# simple-loop-active.net
KiCad netlist of a schematic drawn in EAGLE
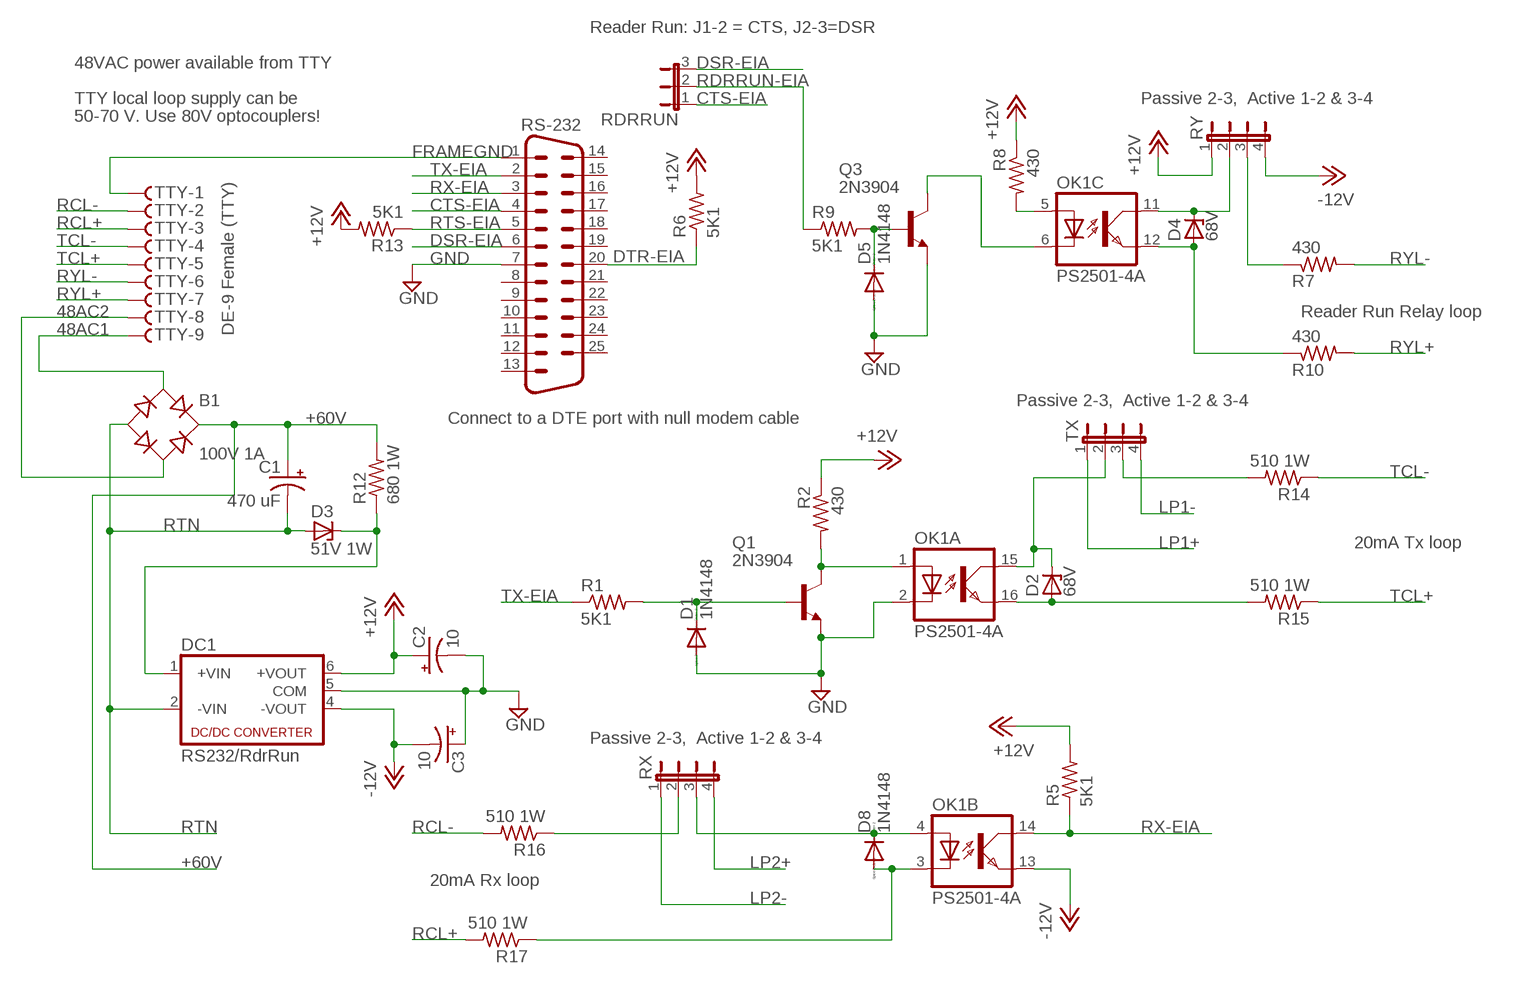
[diagram p0: schematic, sheet 1]
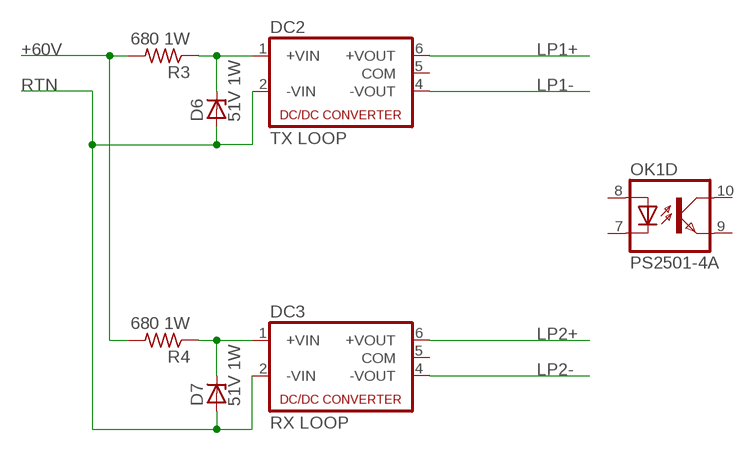
[diagram p1: schematic, sheet 2]

(export (version "E")
  (design (tool "Eeschema 10.0.6"))
  (components
    (comp (ref "D6")
      (value "51V 1W")
      (footprint "eagle-import:DO41Z10")
      (libsource (lib "eagle-import") (part "ZENER-DIODEDO41Z10"))
    )
    (comp (ref "D7")
      (value "51V 1W")
      (footprint "eagle-import:DO41Z10")
      (libsource (lib "eagle-import") (part "ZENER-DIODEDO41Z10"))
    )
    (comp (ref "DC2")
      (value "TX LOOP")
      (footprint "eagle-import:NMA")
      (fields (field (name "MF") "C & D TECHNOLOGIES, INC") (field (name "MPN") "NMA0515SC"))
      (libsource (lib "eagle-import") (part "NMA"))
    )
    (comp (ref "DC3")
      (value "RX LOOP")
      (footprint "eagle-import:NMA")
      (fields (field (name "MF") "C & D TECHNOLOGIES, INC") (field (name "MPN") "NMA0515SC"))
      (libsource (lib "eagle-import") (part "NMA"))
    )
    (comp (ref "OK1")
      (value "PS2501-4A")
      (footprint "eagle-import:DIL16")
      (fields (field (name "MF") "VISHAY/TELEFUNKEN") (field (name "MPN") "ILQ1"))
      (libsource (lib "eagle-import") (part "ILQ1"))
    )
    (comp (ref "R3")
      (value "680 1W")
      (footprint "eagle-import:P0817V")
      (libsource (lib "eagle-import") (part "R-US_0817/7V"))
    )
    (comp (ref "R4")
      (value "680 1W")
      (footprint "eagle-import:P0817V")
      (libsource (lib "eagle-import") (part "R-US_0817/7V"))
    )
    (comp (ref "B1")
      (value "100V 1A")
      (footprint "eagle-import:RB1A")
      (libsource (lib "eagle-import") (part "RB1A"))
    )
    (comp (ref "C1")
      (value "470 uF")
      (footprint "eagle-import:E7,5-18")
      (libsource (lib "eagle-import") (part "CPOL-USE7.5-18"))
    )
    (comp (ref "C2")
      (value "10")
      (footprint "eagle-import:B45181A")
      (libsource (lib "eagle-import") (part "CPOL-USB45181A"))
    )
    (comp (ref "C3")
      (value "10")
      (footprint "eagle-import:B45181A")
      (libsource (lib "eagle-import") (part "CPOL-USB45181A"))
    )
    (comp (ref "D1")
      (value "1N4148")
      (footprint "eagle-import:DO35-10")
      (libsource (lib "eagle-import") (part "1N4148DO35-10"))
    )
    (comp (ref "D2")
      (value "68V")
      (footprint "eagle-import:DO41Z10")
      (libsource (lib "eagle-import") (part "ZENER-DIODEDO41Z10"))
    )
    (comp (ref "D3")
      (value "51V 1W")
      (footprint "eagle-import:DO41Z10")
      (libsource (lib "eagle-import") (part "ZENER-DIODEDO41Z10"))
    )
    (comp (ref "D4")
      (value "68V")
      (footprint "eagle-import:DO41Z10")
      (libsource (lib "eagle-import") (part "ZENER-DIODEDO41Z10"))
    )
    (comp (ref "D5")
      (value "1N4148")
      (footprint "eagle-import:DO35-10")
      (libsource (lib "eagle-import") (part "1N4148DO35-10"))
    )
    (comp (ref "D8")
      (value "1N4148")
      (footprint "eagle-import:DO35-10")
      (libsource (lib "eagle-import") (part "1N4148DO35-10"))
    )
    (comp (ref "DC1")
      (value "RS232/RdrRun")
      (footprint "eagle-import:NMA")
      (fields (field (name "MF") "C & D TECHNOLOGIES, INC") (field (name "MPN") "NMA0515SC"))
      (libsource (lib "eagle-import") (part "NMA"))
    )
    (comp (ref "Q1")
      (value "2N3904")
      (footprint "eagle-import:TO92")
      (libsource (lib "eagle-import") (part "2N3904"))
    )
    (comp (ref "Q3")
      (value "2N3904")
      (footprint "eagle-import:TO92")
      (libsource (lib "eagle-import") (part "2N3904"))
    )
    (comp (ref "R1")
      (value "5K1")
      (footprint "eagle-import:0207_10")
      (libsource (lib "eagle-import") (part "R-US_0207/10"))
    )
    (comp (ref "R2")
      (value "430")
      (footprint "eagle-import:0207_10")
      (libsource (lib "eagle-import") (part "R-US_0207/10"))
    )
    (comp (ref "R5")
      (value "5K1")
      (footprint "eagle-import:0207_10")
      (libsource (lib "eagle-import") (part "R-US_0207/10"))
    )
    (comp (ref "R6")
      (value "5K1")
      (footprint "eagle-import:0207_10")
      (libsource (lib "eagle-import") (part "R-US_0207/10"))
    )
    (comp (ref "R7")
      (value "430")
      (footprint "eagle-import:0207_10")
      (libsource (lib "eagle-import") (part "R-US_0207/10"))
    )
    (comp (ref "R8")
      (value "430")
      (footprint "eagle-import:0207_10")
      (libsource (lib "eagle-import") (part "R-US_0207/10"))
    )
    (comp (ref "R9")
      (value "5K1")
      (footprint "eagle-import:0207_10")
      (libsource (lib "eagle-import") (part "R-US_0207/10"))
    )
    (comp (ref "R10")
      (value "430")
      (footprint "eagle-import:0207_10")
      (libsource (lib "eagle-import") (part "R-US_0207/10"))
    )
    (comp (ref "R12")
      (value "680 1W")
      (footprint "eagle-import:P0817V")
      (libsource (lib "eagle-import") (part "R-US_0817/7V"))
    )
    (comp (ref "R13")
      (value "5K1")
      (footprint "eagle-import:0207_10")
      (libsource (lib "eagle-import") (part "R-US_0207/10"))
    )
    (comp (ref "R14")
      (value "510 1W")
      (footprint "eagle-import:P0817V")
      (libsource (lib "eagle-import") (part "R-US_0817/7V"))
    )
    (comp (ref "R15")
      (value "510 1W")
      (footprint "eagle-import:P0817V")
      (libsource (lib "eagle-import") (part "R-US_0817/7V"))
    )
    (comp (ref "R16")
      (value "510 1W")
      (footprint "eagle-import:P0817V")
      (libsource (lib "eagle-import") (part "R-US_0817/7V"))
    )
    (comp (ref "R17")
      (value "510 1W")
      (footprint "eagle-import:P0817V")
      (libsource (lib "eagle-import") (part "R-US_0817/7V"))
    )
    (comp (ref "RDRRUN")
      (value "JP2E")
      (footprint "eagle-import:JP2")
      (libsource (lib "eagle-import") (part "JP2E"))
    )
    (comp (ref "RS-232")
      (value "M25H")
      (footprint "eagle-import:M25H")
      (libsource (lib "eagle-import") (part "M25H"))
    )
    (comp (ref "RX")
      (value "JP4E")
      (footprint "eagle-import:JP4")
      (libsource (lib "eagle-import") (part "JP4E"))
    )
    (comp (ref "RY")
      (value "JP4E")
      (footprint "eagle-import:JP4")
      (libsource (lib "eagle-import") (part "JP4E"))
    )
    (comp (ref "TTY")
      (value "F09HS")
      (footprint "eagle-import:F09H")
      (libsource (lib "eagle-import") (part "F09?SH"))
    )
    (comp (ref "TX")
      (value "JP4E")
      (footprint "eagle-import:JP4")
      (libsource (lib "eagle-import") (part "JP4E"))
    )
  )
  (nets
    (net (code "1") (name "+12V") (class "Default")
      (node (ref "C2") (pin "+") (pinfunction "+_+") (pintype "passive"))
      (node (ref "DC1") (pin "6") (pinfunction "+VOUT_6") (pintype "passive"))
      (node (ref "R13") (pin "2") (pinfunction "2_2") (pintype "passive"))
      (node (ref "R2") (pin "1") (pinfunction "1_1") (pintype "passive"))
      (node (ref "R5") (pin "2") (pinfunction "2_2") (pintype "passive"))
      (node (ref "R6") (pin "2") (pinfunction "2_2") (pintype "passive"))
      (node (ref "R8") (pin "1") (pinfunction "1_1") (pintype "passive"))
      (node (ref "RY") (pin "1") (pinfunction "1_1") (pintype "passive"))
    )
    (net (code "2") (name "+60V") (class "Default")
      (node (ref "B1") (pin "+") (pinfunction "+_+") (pintype "passive"))
      (node (ref "C1") (pin "+") (pinfunction "+_+") (pintype "passive"))
      (node (ref "R12") (pin "2") (pinfunction "2_2") (pintype "passive"))
      (node (ref "R3") (pin "2") (pinfunction "2_2") (pintype "passive"))
      (node (ref "R4") (pin "2") (pinfunction "2_2") (pintype "passive"))
    )
    (net (code "3") (name "-12V") (class "Default")
      (node (ref "C3") (pin "-") (pinfunction "-_-") (pintype "passive"))
      (node (ref "DC1") (pin "4") (pinfunction "-VOUT_4") (pintype "passive"))
      (node (ref "OK1") (pin "13") (pinfunction "EMIT_13") (pintype "passive"))
      (node (ref "RY") (pin "4") (pinfunction "4_4") (pintype "passive"))
    )
    (net (code "4") (name "48AC1") (class "Default")
      (node (ref "B1") (pin "AC1") (pinfunction "AC1_AC1") (pintype "passive"))
      (node (ref "TTY") (pin "9") (pinfunction "F_9") (pintype "passive"))
    )
    (net (code "5") (name "48AC2") (class "Default")
      (node (ref "B1") (pin "AC2") (pinfunction "AC2_AC2") (pintype "passive"))
      (node (ref "TTY") (pin "8") (pinfunction "F_8") (pintype "passive"))
    )
    (net (code "6") (name "CTS-EIA") (class "Default")
      (node (ref "RDRRUN") (pin "1") (pinfunction "1_1") (pintype "passive"))
      (node (ref "RS-232") (pin "4") (pinfunction "4_4") (pintype "passive"))
    )
    (net (code "7") (name "DSR-EIA") (class "Default")
      (node (ref "RDRRUN") (pin "3") (pinfunction "3_3") (pintype "passive"))
      (node (ref "RS-232") (pin "6") (pinfunction "6_6") (pintype "passive"))
    )
    (net (code "8") (name "DTR-EIA") (class "Default")
      (node (ref "R6") (pin "1") (pinfunction "1_1") (pintype "passive"))
      (node (ref "RS-232") (pin "20") (pinfunction "20_20") (pintype "passive"))
    )
    (net (code "9") (name "FRAMEGND") (class "Default")
      (node (ref "RS-232") (pin "1") (pinfunction "1_1") (pintype "passive"))
      (node (ref "TTY") (pin "1") (pinfunction "F_1") (pintype "passive"))
    )
    (net (code "10") (name "GND") (class "Default")
      (node (ref "C2") (pin "-") (pinfunction "-_-") (pintype "passive"))
      (node (ref "C3") (pin "+") (pinfunction "+_+") (pintype "passive"))
      (node (ref "D1") (pin "A") (pinfunction "A_A") (pintype "passive"))
      (node (ref "D5") (pin "A") (pinfunction "A_A") (pintype "passive"))
      (node (ref "DC1") (pin "5") (pinfunction "COM_5") (pintype "passive"))
      (node (ref "OK1") (pin "2") (pinfunction "C_2") (pintype "passive"))
      (node (ref "Q1") (pin "3") (pinfunction "E_3") (pintype "passive"))
      (node (ref "Q3") (pin "3") (pinfunction "E_3") (pintype "passive"))
      (node (ref "RS-232") (pin "7") (pinfunction "7_7") (pintype "passive"))
    )
    (net (code "11") (name "LP1+") (class "Default")
      (node (ref "DC2") (pin "6") (pinfunction "+VOUT_6") (pintype "passive"))
      (node (ref "TX") (pin "1") (pinfunction "1_1") (pintype "passive"))
    )
    (net (code "12") (name "LP1-") (class "Default")
      (node (ref "DC2") (pin "4") (pinfunction "-VOUT_4") (pintype "passive"))
      (node (ref "TX") (pin "4") (pinfunction "4_4") (pintype "passive"))
    )
    (net (code "13") (name "LP2+") (class "Default")
      (node (ref "DC3") (pin "6") (pinfunction "+VOUT_6") (pintype "passive"))
      (node (ref "RX") (pin "4") (pinfunction "4_4") (pintype "passive"))
    )
    (net (code "14") (name "LP2-") (class "Default")
      (node (ref "DC3") (pin "4") (pinfunction "-VOUT_4") (pintype "passive"))
      (node (ref "RX") (pin "1") (pinfunction "1_1") (pintype "passive"))
    )
    (net (code "15") (name "Net-(DC1-+VIN)") (class "Default")
      (node (ref "D3") (pin "C") (pinfunction "C_C") (pintype "passive"))
      (node (ref "DC1") (pin "1") (pinfunction "+VIN_1") (pintype "passive"))
      (node (ref "R12") (pin "1") (pinfunction "1_1") (pintype "passive"))
    )
    (net (code "16") (name "Net-(DC2-+VIN)") (class "Default")
      (node (ref "D6") (pin "C") (pinfunction "C_C") (pintype "passive"))
      (node (ref "DC2") (pin "1") (pinfunction "+VIN_1") (pintype "passive"))
      (node (ref "R3") (pin "1") (pinfunction "1_1") (pintype "passive"))
    )
    (net (code "17") (name "Net-(DC3-+VIN)") (class "Default")
      (node (ref "D7") (pin "C") (pinfunction "C_C") (pintype "passive"))
      (node (ref "DC3") (pin "1") (pinfunction "+VIN_1") (pintype "passive"))
      (node (ref "R4") (pin "1") (pinfunction "1_1") (pintype "passive"))
    )
    (net (code "18") (name "Net-(OK1A-A)") (class "Default")
      (node (ref "OK1") (pin "1") (pinfunction "A_1") (pintype "passive"))
      (node (ref "Q1") (pin "1") (pinfunction "C_1") (pintype "passive"))
      (node (ref "R2") (pin "2") (pinfunction "2_2") (pintype "passive"))
    )
    (net (code "19") (name "Net-(OK1A-COL)") (class "Default")
      (node (ref "D2") (pin "C") (pinfunction "C_C") (pintype "passive"))
      (node (ref "OK1") (pin "15") (pinfunction "COL_15") (pintype "passive"))
      (node (ref "TX") (pin "2") (pinfunction "2_2") (pintype "passive"))
    )
    (net (code "20") (name "Net-(OK1A-EMIT)") (class "Default")
      (node (ref "D2") (pin "A") (pinfunction "A_A") (pintype "passive"))
      (node (ref "OK1") (pin "16") (pinfunction "EMIT_16") (pintype "passive"))
      (node (ref "R15") (pin "2") (pinfunction "2_2") (pintype "passive"))
    )
    (net (code "21") (name "Net-(OK1B-A)") (class "Default")
      (node (ref "D8") (pin "C") (pinfunction "C_C") (pintype "passive"))
      (node (ref "OK1") (pin "4") (pinfunction "A_4") (pintype "passive"))
      (node (ref "RX") (pin "3") (pinfunction "3_3") (pintype "passive"))
    )
    (net (code "22") (name "Net-(OK1B-C)") (class "Default")
      (node (ref "D8") (pin "A") (pinfunction "A_A") (pintype "passive"))
      (node (ref "OK1") (pin "3") (pinfunction "C_3") (pintype "passive"))
      (node (ref "R17") (pin "1") (pinfunction "1_1") (pintype "passive"))
    )
    (net (code "23") (name "Net-(OK1C-A)") (class "Default")
      (node (ref "OK1") (pin "5") (pinfunction "A_5") (pintype "passive"))
      (node (ref "R8") (pin "2") (pinfunction "2_2") (pintype "passive"))
    )
    (net (code "24") (name "Net-(OK1C-C)") (class "Default")
      (node (ref "OK1") (pin "6") (pinfunction "C_6") (pintype "passive"))
      (node (ref "Q3") (pin "1") (pinfunction "C_1") (pintype "passive"))
    )
    (net (code "25") (name "Net-(OK1C-COL)") (class "Default")
      (node (ref "D4") (pin "C") (pinfunction "C_C") (pintype "passive"))
      (node (ref "OK1") (pin "11") (pinfunction "COL_11") (pintype "passive"))
      (node (ref "RY") (pin "2") (pinfunction "2_2") (pintype "passive"))
    )
    (net (code "26") (name "Net-(OK1C-EMIT)") (class "Default")
      (node (ref "D4") (pin "A") (pinfunction "A_A") (pintype "passive"))
      (node (ref "OK1") (pin "12") (pinfunction "EMIT_12") (pintype "passive"))
      (node (ref "R10") (pin "1") (pinfunction "1_1") (pintype "passive"))
    )
    (net (code "27") (name "Net-(Q1-B)") (class "Default")
      (node (ref "D1") (pin "C") (pinfunction "C_C") (pintype "passive"))
      (node (ref "Q1") (pin "2") (pinfunction "B_2") (pintype "passive"))
      (node (ref "R1") (pin "2") (pinfunction "2_2") (pintype "passive"))
    )
    (net (code "28") (name "Net-(Q3-B)") (class "Default")
      (node (ref "D5") (pin "C") (pinfunction "C_C") (pintype "passive"))
      (node (ref "Q3") (pin "2") (pinfunction "B_2") (pintype "passive"))
      (node (ref "R9") (pin "2") (pinfunction "2_2") (pintype "passive"))
    )
    (net (code "29") (name "Net-(R7-Pad1)") (class "Default")
      (node (ref "R7") (pin "1") (pinfunction "1_1") (pintype "passive"))
      (node (ref "RY") (pin "3") (pinfunction "3_3") (pintype "passive"))
    )
    (net (code "30") (name "Net-(R14-Pad2)") (class "Default")
      (node (ref "R14") (pin "2") (pinfunction "2_2") (pintype "passive"))
      (node (ref "TX") (pin "3") (pinfunction "3_3") (pintype "passive"))
    )
    (net (code "31") (name "Net-(R16-Pad1)") (class "Default")
      (node (ref "R16") (pin "1") (pinfunction "1_1") (pintype "passive"))
      (node (ref "RX") (pin "2") (pinfunction "2_2") (pintype "passive"))
    )
    (net (code "32") (name "RCL+") (class "Default")
      (node (ref "R17") (pin "2") (pinfunction "2_2") (pintype "passive"))
      (node (ref "TTY") (pin "3") (pinfunction "F_3") (pintype "passive"))
    )
    (net (code "33") (name "RCL-") (class "Default")
      (node (ref "R16") (pin "2") (pinfunction "2_2") (pintype "passive"))
      (node (ref "TTY") (pin "2") (pinfunction "F_2") (pintype "passive"))
    )
    (net (code "34") (name "RDRRUN-EIA") (class "Default")
      (node (ref "R9") (pin "1") (pinfunction "1_1") (pintype "passive"))
      (node (ref "RDRRUN") (pin "2") (pinfunction "2_2") (pintype "passive"))
    )
    (net (code "35") (name "RTN") (class "Default")
      (node (ref "B1") (pin "-") (pinfunction "-_-") (pintype "passive"))
      (node (ref "C1") (pin "-") (pinfunction "-_-") (pintype "passive"))
      (node (ref "D3") (pin "A") (pinfunction "A_A") (pintype "passive"))
      (node (ref "D6") (pin "A") (pinfunction "A_A") (pintype "passive"))
      (node (ref "D7") (pin "A") (pinfunction "A_A") (pintype "passive"))
      (node (ref "DC1") (pin "2") (pinfunction "-VIN_2") (pintype "passive"))
      (node (ref "DC2") (pin "2") (pinfunction "-VIN_2") (pintype "passive"))
      (node (ref "DC3") (pin "2") (pinfunction "-VIN_2") (pintype "passive"))
    )
    (net (code "36") (name "RTS-EIA") (class "Default")
      (node (ref "R13") (pin "1") (pinfunction "1_1") (pintype "passive"))
      (node (ref "RS-232") (pin "5") (pinfunction "5_5") (pintype "passive"))
    )
    (net (code "37") (name "RX-EIA") (class "Default")
      (node (ref "OK1") (pin "14") (pinfunction "COL_14") (pintype "passive"))
      (node (ref "R5") (pin "1") (pinfunction "1_1") (pintype "passive"))
      (node (ref "RS-232") (pin "3") (pinfunction "3_3") (pintype "passive"))
    )
    (net (code "38") (name "RYL+") (class "Default")
      (node (ref "R10") (pin "2") (pinfunction "2_2") (pintype "passive"))
      (node (ref "TTY") (pin "7") (pinfunction "F_7") (pintype "passive"))
    )
    (net (code "39") (name "RYL-") (class "Default")
      (node (ref "R7") (pin "2") (pinfunction "2_2") (pintype "passive"))
      (node (ref "TTY") (pin "6") (pinfunction "F_6") (pintype "passive"))
    )
    (net (code "40") (name "TCL+") (class "Default")
      (node (ref "R15") (pin "1") (pinfunction "1_1") (pintype "passive"))
      (node (ref "TTY") (pin "5") (pinfunction "F_5") (pintype "passive"))
    )
    (net (code "41") (name "TCL-") (class "Default")
      (node (ref "R14") (pin "1") (pinfunction "1_1") (pintype "passive"))
      (node (ref "TTY") (pin "4") (pinfunction "F_4") (pintype "passive"))
    )
    (net (code "42") (name "TX-EIA") (class "Default")
      (node (ref "R1") (pin "1") (pinfunction "1_1") (pintype "passive"))
      (node (ref "RS-232") (pin "2") (pinfunction "2_2") (pintype "passive"))
    )
    (net (code "43") (name "unconnected-(DC2-COM-Pad5)") (class "Default")
      (node (ref "DC2") (pin "5") (pinfunction "COM_5") (pintype "passive"))
    )
    (net (code "44") (name "unconnected-(DC3-COM-Pad5)") (class "Default")
      (node (ref "DC3") (pin "5") (pinfunction "COM_5") (pintype "passive"))
    )
    (net (code "45") (name "unconnected-(OK1D-A-Pad8)") (class "Default")
      (node (ref "OK1") (pin "8") (pinfunction "A_8") (pintype "passive"))
    )
    (net (code "46") (name "unconnected-(OK1D-C-Pad7)") (class "Default")
      (node (ref "OK1") (pin "7") (pinfunction "C_7") (pintype "passive"))
    )
    (net (code "47") (name "unconnected-(OK1D-COL-Pad10)") (class "Default")
      (node (ref "OK1") (pin "10") (pinfunction "COL_10") (pintype "passive"))
    )
    (net (code "48") (name "unconnected-(OK1D-EMIT-Pad9)") (class "Default")
      (node (ref "OK1") (pin "9") (pinfunction "EMIT_9") (pintype "passive"))
    )
    (net (code "49") (name "unconnected-(RS-232-Pad8)") (class "Default")
      (node (ref "RS-232") (pin "8") (pinfunction "8_8") (pintype "passive"))
    )
    (net (code "50") (name "unconnected-(RS-232-Pad9)") (class "Default")
      (node (ref "RS-232") (pin "9") (pinfunction "9_9") (pintype "passive"))
    )
    (net (code "51") (name "unconnected-(RS-232-Pad10)") (class "Default")
      (node (ref "RS-232") (pin "10") (pinfunction "10_10") (pintype "passive"))
    )
    (net (code "52") (name "unconnected-(RS-232-Pad11)") (class "Default")
      (node (ref "RS-232") (pin "11") (pinfunction "11_11") (pintype "passive"))
    )
    (net (code "53") (name "unconnected-(RS-232-Pad12)") (class "Default")
      (node (ref "RS-232") (pin "12") (pinfunction "12_12") (pintype "passive"))
    )
    (net (code "54") (name "unconnected-(RS-232-Pad13)") (class "Default")
      (node (ref "RS-232") (pin "13") (pinfunction "13_13") (pintype "passive"))
    )
    (net (code "55") (name "unconnected-(RS-232-Pad14)") (class "Default")
      (node (ref "RS-232") (pin "14") (pinfunction "14_14") (pintype "passive"))
    )
    (net (code "56") (name "unconnected-(RS-232-Pad15)") (class "Default")
      (node (ref "RS-232") (pin "15") (pinfunction "15_15") (pintype "passive"))
    )
    (net (code "57") (name "unconnected-(RS-232-Pad16)") (class "Default")
      (node (ref "RS-232") (pin "16") (pinfunction "16_16") (pintype "passive"))
    )
    (net (code "58") (name "unconnected-(RS-232-Pad17)") (class "Default")
      (node (ref "RS-232") (pin "17") (pinfunction "17_17") (pintype "passive"))
    )
    (net (code "59") (name "unconnected-(RS-232-Pad18)") (class "Default")
      (node (ref "RS-232") (pin "18") (pinfunction "18_18") (pintype "passive"))
    )
    (net (code "60") (name "unconnected-(RS-232-Pad19)") (class "Default")
      (node (ref "RS-232") (pin "19") (pinfunction "19_19") (pintype "passive"))
    )
    (net (code "61") (name "unconnected-(RS-232-Pad21)") (class "Default")
      (node (ref "RS-232") (pin "21") (pinfunction "21_21") (pintype "passive"))
    )
    (net (code "62") (name "unconnected-(RS-232-Pad22)") (class "Default")
      (node (ref "RS-232") (pin "22") (pinfunction "22_22") (pintype "passive"))
    )
    (net (code "63") (name "unconnected-(RS-232-Pad23)") (class "Default")
      (node (ref "RS-232") (pin "23") (pinfunction "23_23") (pintype "passive"))
    )
    (net (code "64") (name "unconnected-(RS-232-Pad24)") (class "Default")
      (node (ref "RS-232") (pin "24") (pinfunction "24_24") (pintype "passive"))
    )
    (net (code "65") (name "unconnected-(RS-232-Pad25)") (class "Default")
      (node (ref "RS-232") (pin "25") (pinfunction "25_25") (pintype "passive"))
    )
  )
)
